# share.net
KiCad netlist of a schematic drawn in EasyEDA
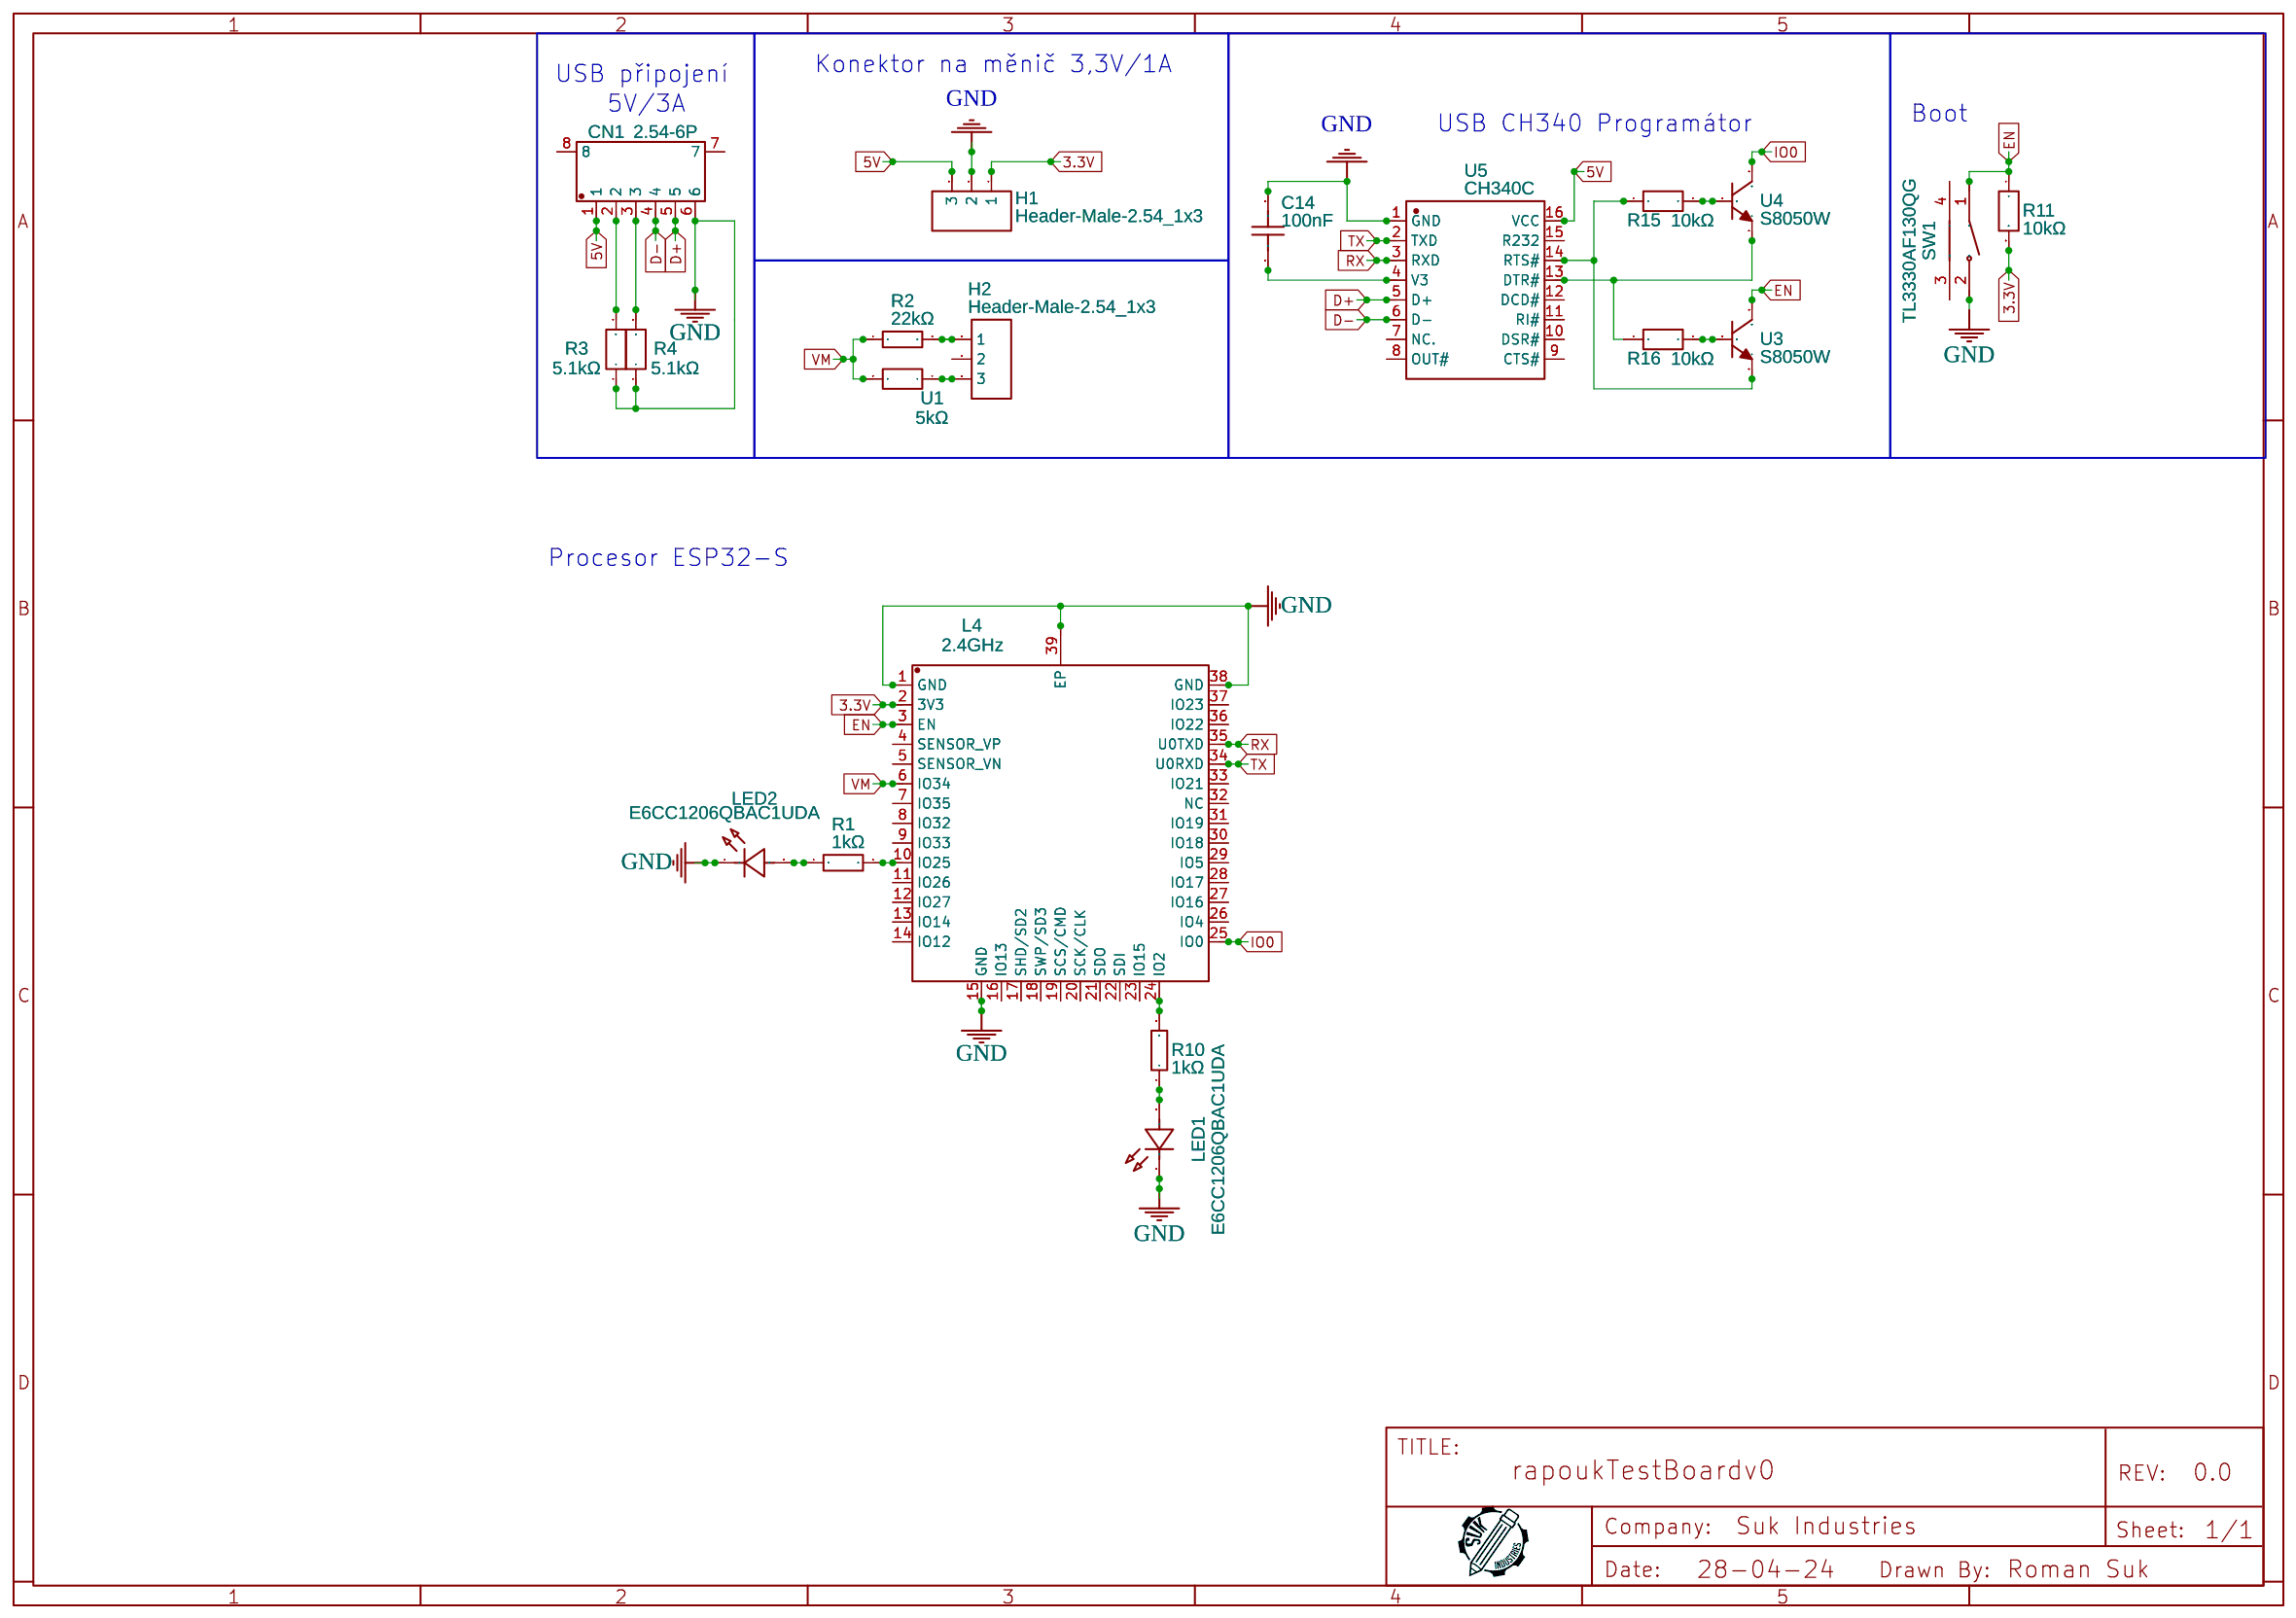
[diagram p0: schematic sheet]

(export (version "E")
  (design (tool "Eeschema 10.0.6"))
  (components
    (comp (ref "C14")
      (value "100nF")
      (fields
        (field (name "Manufacturer Part") "1206Y1000104KXR")
        (field (name "Manufacturer") "Knowles(楼氏)")
      )
      (libsource (lib "") (part "1206Y1000104KXR"))
    )
    (comp (ref "CN1")
      (value "2.54-6P")
      (fields (field (name "Manufacturer Part") "XH-6P卧贴") (field (name "Manufacturer") "BOOMELE(博穆精密)"))
      (libsource (lib "") (part "2.54-6P"))
    )
    (comp (ref "H1")
      (value "Header-Male-2.54_1x3")
      (fields (field (name "Manufacturer Part") "2.54-1*3P针") (field (name "Manufacturer") "BOOMELE(博穆精密)"))
      (libsource (lib "") (part "Header-Male-2.54_1x3_1"))
    )
    (comp (ref "H2")
      (value "Header-Male-2.54_1x3")
      (fields (field (name "Manufacturer Part") "2.54-1*3P针") (field (name "Manufacturer") "BOOMELE(博穆精密)"))
      (libsource (lib "") (part "Header-Male-2.54_1x3"))
    )
    (comp (ref "L4")
      (value "2.4GHz")
      (fields
        (field (name "Manufacturer Part") "ESP32-S(16MB)")
        (field (name "Manufacturer") "Ai-Thinker(安信可)")
      )
      (libsource (lib "") (part "ESP32-S(16MB)"))
    )
    (comp (ref "LED1")
      (value "E6CC1206QBAC1UDA")
      (fields (field (name "Manufacturer") "ekinglux(亿晶源)"))
      (libsource (lib "") (part "E6CC1206QBAC1UDA_1"))
    )
    (comp (ref "LED2")
      (value "E6CC1206QBAC1UDA")
      (fields (field (name "Manufacturer") "ekinglux(亿晶源)"))
      (libsource (lib "") (part "E6CC1206QBAC1UDA"))
    )
    (comp (ref "R1")
      (value "1kΩ")
      (fields (field (name "Manufacturer Part") "CR1206-FX-1001ELF") (field (name "Manufacturer") "BOURNS"))
      (libsource (lib "") (part "CR1206-FX-1001ELF"))
    )
    (comp (ref "R2")
      (value "22kΩ")
      (fields (field (name "Manufacturer Part") "AECR1206F22K0K9") (field (name "Manufacturer") "RESI(开步睿思）"))
      (libsource (lib "") (part "AECR1206F22K0K9"))
    )
    (comp (ref "R3")
      (value "5.1kΩ")
      (fields (field (name "Manufacturer Part") "FRC0603F5101TS") (field (name "Manufacturer") "FOJAN(富捷)"))
      (libsource (lib "") (part "FRC0603F5101TS"))
    )
    (comp (ref "R4")
      (value "5.1kΩ")
      (fields (field (name "Manufacturer Part") "FRC0603F5101TS") (field (name "Manufacturer") "FOJAN(富捷)"))
      (libsource (lib "") (part "FRC0603F5101TS"))
    )
    (comp (ref "R10")
      (value "1kΩ")
      (fields (field (name "Manufacturer Part") "CR1206-FX-1001ELF") (field (name "Manufacturer") "BOURNS"))
      (libsource (lib "") (part "CR1206-FX-1001ELF_1"))
    )
    (comp (ref "R11")
      (value "10kΩ")
      (fields (field (name "Manufacturer Part") "SCR1206F10K") (field (name "Manufacturer") "VO(翔胜)"))
      (libsource (lib "") (part "SCR1206F10K_1"))
    )
    (comp (ref "R15")
      (value "10kΩ")
      (fields (field (name "Manufacturer Part") "SCR1206F10K") (field (name "Manufacturer") "VO(翔胜)"))
      (libsource (lib "") (part "SCR1206F10K"))
    )
    (comp (ref "R16")
      (value "10kΩ")
      (fields (field (name "Manufacturer Part") "SCR1206F10K") (field (name "Manufacturer") "VO(翔胜)"))
      (libsource (lib "") (part "SCR1206F10K"))
    )
    (comp (ref "SW1")
      (value "TL3330AF130QG")
      (fields (field (name "Manufacturer") "E-Switch"))
      (libsource (lib "") (part "TL3330AF130QG"))
    )
    (comp (ref "U1")
      (value "5kΩ")
      (fields (field (name "Manufacturer Part") "HVF1206T5001FE") (field (name "Manufacturer") "Ohmite"))
      (libsource (lib "") (part "HVF1206T5001FE"))
    )
    (comp (ref "U3")
      (value "S8050W")
      (fields (field (name "Manufacturer") "Slkor(萨科微)"))
      (libsource (lib "") (part "S8050W"))
    )
    (comp (ref "U4")
      (value "S8050W")
      (fields (field (name "Manufacturer") "Slkor(萨科微)"))
      (libsource (lib "") (part "S8050W"))
    )
    (comp (ref "U5")
      (value "CH340C")
      (fields (field (name "Manufacturer") "WCH(南京沁恒)"))
      (libsource (lib "") (part "CH340C"))
    )
  )
  (nets
    (net (code "1") (name "3.3V") (class "Default")
      (node (ref "H1") (pin "1") (pinfunction "1_1") (pintype "input"))
      (node (ref "L4") (pin "2") (pinfunction "3V3_2") (pintype "unspecified"))
      (node (ref "R11") (pin "2") (pinfunction "2_2") (pintype "unspecified"))
    )
    (net (code "2") (name "5V") (class "Default")
      (node (ref "CN1") (pin "1") (pinfunction "1_1") (pintype "unspecified"))
      (node (ref "H1") (pin "3") (pinfunction "3_3") (pintype "input"))
      (node (ref "U5") (pin "16") (pinfunction "VCC_16") (pintype "unspecified"))
    )
    (net (code "3") (name "D+") (class "Default")
      (node (ref "CN1") (pin "5") (pinfunction "5_5") (pintype "unspecified"))
      (node (ref "U5") (pin "5") (pinfunction "D+_5") (pintype "unspecified"))
    )
    (net (code "4") (name "D-") (class "Default")
      (node (ref "CN1") (pin "4") (pinfunction "4_4") (pintype "unspecified"))
      (node (ref "U5") (pin "6") (pinfunction "D-_6") (pintype "unspecified"))
    )
    (net (code "5") (name "EN") (class "Default")
      (node (ref "L4") (pin "3") (pinfunction "EN_3") (pintype "unspecified"))
      (node (ref "R11") (pin "1") (pinfunction "1_1") (pintype "unspecified"))
      (node (ref "SW1") (pin "1") (pinfunction "1_1") (pintype "unspecified"))
      (node (ref "U3") (pin "3") (pinfunction "C_3") (pintype "unspecified"))
    )
    (net (code "6") (name "GND") (class "Default")
      (node (ref "C14") (pin "2") (pinfunction "2_2") (pintype "unspecified"))
      (node (ref "CN1") (pin "6") (pinfunction "6_6") (pintype "unspecified"))
      (node (ref "H1") (pin "2") (pinfunction "2_2") (pintype "input"))
      (node (ref "L4") (pin "1") (pinfunction "GND_1") (pintype "unspecified"))
      (node (ref "L4") (pin "15") (pinfunction "GND_15") (pintype "unspecified"))
      (node (ref "L4") (pin "38") (pinfunction "GND_38") (pintype "unspecified"))
      (node (ref "L4") (pin "39") (pinfunction "EP_39") (pintype "unspecified"))
      (node (ref "LED1") (pin "1") (pinfunction "K_1") (pintype "unspecified"))
      (node (ref "LED2") (pin "1") (pinfunction "K_1") (pintype "unspecified"))
      (node (ref "R3") (pin "1") (pinfunction "1_1") (pintype "unspecified"))
      (node (ref "R4") (pin "1") (pinfunction "1_1") (pintype "unspecified"))
      (node (ref "SW1") (pin "2") (pinfunction "2_2") (pintype "unspecified"))
      (node (ref "U5") (pin "1") (pinfunction "GND_1") (pintype "unspecified"))
    )
    (net (code "7") (name "IO0") (class "Default")
      (node (ref "L4") (pin "25") (pinfunction "IO0_25") (pintype "unspecified"))
      (node (ref "U4") (pin "3") (pinfunction "C_3") (pintype "unspecified"))
    )
    (net (code "8") (name "Net-(CN1-Pad2)") (class "Default")
      (node (ref "CN1") (pin "2") (pinfunction "2_2") (pintype "unspecified"))
      (node (ref "R3") (pin "2") (pinfunction "2_2") (pintype "unspecified"))
    )
    (net (code "9") (name "Net-(CN1-Pad3)") (class "Default")
      (node (ref "CN1") (pin "3") (pinfunction "3_3") (pintype "unspecified"))
      (node (ref "R4") (pin "2") (pinfunction "2_2") (pintype "unspecified"))
    )
    (net (code "10") (name "Net-(H2-Pad1)") (class "Default")
      (node (ref "H2") (pin "1") (pinfunction "1_1") (pintype "input"))
      (node (ref "R2") (pin "2") (pinfunction "2_2") (pintype "unspecified"))
    )
    (net (code "11") (name "Net-(H2-Pad3)") (class "Default")
      (node (ref "H2") (pin "3") (pinfunction "3_3") (pintype "input"))
      (node (ref "U1") (pin "1") (pinfunction "1_1") (pintype "unspecified"))
    )
    (net (code "12") (name "Net-(L4-IO2)") (class "Default")
      (node (ref "L4") (pin "24") (pinfunction "IO2_24") (pintype "unspecified"))
      (node (ref "R10") (pin "2") (pinfunction "2_2") (pintype "unspecified"))
    )
    (net (code "13") (name "Net-(L4-IO25)") (class "Default")
      (node (ref "L4") (pin "10") (pinfunction "IO25_10") (pintype "unspecified"))
      (node (ref "R1") (pin "2") (pinfunction "2_2") (pintype "unspecified"))
    )
    (net (code "14") (name "Net-(LED1-A)") (class "Default")
      (node (ref "LED1") (pin "2") (pinfunction "A_2") (pintype "unspecified"))
      (node (ref "R10") (pin "1") (pinfunction "1_1") (pintype "unspecified"))
    )
    (net (code "15") (name "Net-(LED2-A)") (class "Default")
      (node (ref "LED2") (pin "2") (pinfunction "A_2") (pintype "unspecified"))
      (node (ref "R1") (pin "1") (pinfunction "1_1") (pintype "unspecified"))
    )
    (net (code "16") (name "Net-(U3-B)") (class "Default")
      (node (ref "R16") (pin "2") (pinfunction "2_2") (pintype "unspecified"))
      (node (ref "U3") (pin "1") (pinfunction "B_1") (pintype "unspecified"))
    )
    (net (code "17") (name "Net-(U3-E)") (class "Default")
      (node (ref "R15") (pin "1") (pinfunction "1_1") (pintype "unspecified"))
      (node (ref "U3") (pin "2") (pinfunction "E_2") (pintype "unspecified"))
      (node (ref "U5") (pin "14") (pinfunction "RTS#_14") (pintype "unspecified"))
    )
    (net (code "18") (name "Net-(U4-B)") (class "Default")
      (node (ref "R15") (pin "2") (pinfunction "2_2") (pintype "unspecified"))
      (node (ref "U4") (pin "1") (pinfunction "B_1") (pintype "unspecified"))
    )
    (net (code "19") (name "Net-(U4-E)") (class "Default")
      (node (ref "R16") (pin "1") (pinfunction "1_1") (pintype "unspecified"))
      (node (ref "U4") (pin "2") (pinfunction "E_2") (pintype "unspecified"))
      (node (ref "U5") (pin "13") (pinfunction "DTR#_13") (pintype "unspecified"))
    )
    (net (code "20") (name "Net-(U5-V3)") (class "Default")
      (node (ref "C14") (pin "1") (pinfunction "1_1") (pintype "unspecified"))
      (node (ref "U5") (pin "4") (pinfunction "V3_4") (pintype "unspecified"))
    )
    (net (code "21") (name "RX") (class "Default")
      (node (ref "L4") (pin "35") (pinfunction "U0TXD_35") (pintype "unspecified"))
      (node (ref "U5") (pin "3") (pinfunction "RXD_3") (pintype "unspecified"))
    )
    (net (code "22") (name "TX") (class "Default")
      (node (ref "L4") (pin "34") (pinfunction "U0RXD_34") (pintype "unspecified"))
      (node (ref "U5") (pin "2") (pinfunction "TXD_2") (pintype "unspecified"))
    )
    (net (code "23") (name "VM") (class "Default")
      (node (ref "L4") (pin "6") (pinfunction "IO34_6") (pintype "unspecified"))
      (node (ref "R2") (pin "1") (pinfunction "1_1") (pintype "unspecified"))
      (node (ref "U1") (pin "2") (pinfunction "2_2") (pintype "unspecified"))
    )
    (net (code "24") (name "unconnected-(CN1-Pad7)") (class "Default")
      (node (ref "CN1") (pin "7") (pinfunction "7_7") (pintype "unspecified"))
    )
    (net (code "25") (name "unconnected-(CN1-Pad8)") (class "Default")
      (node (ref "CN1") (pin "8") (pinfunction "8_8") (pintype "unspecified"))
    )
    (net (code "26") (name "unconnected-(H2-Pad2)") (class "Default")
      (node (ref "H2") (pin "2") (pinfunction "2_2") (pintype "input"))
    )
    (net (code "27") (name "unconnected-(L4-IO4-Pad26)") (class "Default")
      (node (ref "L4") (pin "26") (pinfunction "IO4_26") (pintype "unspecified"))
    )
    (net (code "28") (name "unconnected-(L4-IO5-Pad29)") (class "Default")
      (node (ref "L4") (pin "29") (pinfunction "IO5_29") (pintype "unspecified"))
    )
    (net (code "29") (name "unconnected-(L4-IO12-Pad14)") (class "Default")
      (node (ref "L4") (pin "14") (pinfunction "IO12_14") (pintype "unspecified"))
    )
    (net (code "30") (name "unconnected-(L4-IO13-Pad16)") (class "Default")
      (node (ref "L4") (pin "16") (pinfunction "IO13_16") (pintype "unspecified"))
    )
    (net (code "31") (name "unconnected-(L4-IO14-Pad13)") (class "Default")
      (node (ref "L4") (pin "13") (pinfunction "IO14_13") (pintype "unspecified"))
    )
    (net (code "32") (name "unconnected-(L4-IO15-Pad23)") (class "Default")
      (node (ref "L4") (pin "23") (pinfunction "IO15_23") (pintype "unspecified"))
    )
    (net (code "33") (name "unconnected-(L4-IO16-Pad27)") (class "Default")
      (node (ref "L4") (pin "27") (pinfunction "IO16_27") (pintype "unspecified"))
    )
    (net (code "34") (name "unconnected-(L4-IO17-Pad28)") (class "Default")
      (node (ref "L4") (pin "28") (pinfunction "IO17_28") (pintype "unspecified"))
    )
    (net (code "35") (name "unconnected-(L4-IO18-Pad30)") (class "Default")
      (node (ref "L4") (pin "30") (pinfunction "IO18_30") (pintype "unspecified"))
    )
    (net (code "36") (name "unconnected-(L4-IO19-Pad31)") (class "Default")
      (node (ref "L4") (pin "31") (pinfunction "IO19_31") (pintype "unspecified"))
    )
    (net (code "37") (name "unconnected-(L4-IO21-Pad33)") (class "Default")
      (node (ref "L4") (pin "33") (pinfunction "IO21_33") (pintype "unspecified"))
    )
    (net (code "38") (name "unconnected-(L4-IO22-Pad36)") (class "Default")
      (node (ref "L4") (pin "36") (pinfunction "IO22_36") (pintype "unspecified"))
    )
    (net (code "39") (name "unconnected-(L4-IO23-Pad37)") (class "Default")
      (node (ref "L4") (pin "37") (pinfunction "IO23_37") (pintype "unspecified"))
    )
    (net (code "40") (name "unconnected-(L4-IO26-Pad11)") (class "Default")
      (node (ref "L4") (pin "11") (pinfunction "IO26_11") (pintype "unspecified"))
    )
    (net (code "41") (name "unconnected-(L4-IO27-Pad12)") (class "Default")
      (node (ref "L4") (pin "12") (pinfunction "IO27_12") (pintype "unspecified"))
    )
    (net (code "42") (name "unconnected-(L4-IO32-Pad8)") (class "Default")
      (node (ref "L4") (pin "8") (pinfunction "IO32_8") (pintype "unspecified"))
    )
    (net (code "43") (name "unconnected-(L4-IO33-Pad9)") (class "Default")
      (node (ref "L4") (pin "9") (pinfunction "IO33_9") (pintype "unspecified"))
    )
    (net (code "44") (name "unconnected-(L4-IO35-Pad7)") (class "Default")
      (node (ref "L4") (pin "7") (pinfunction "IO35_7") (pintype "unspecified"))
    )
    (net (code "45") (name "unconnected-(L4-NC-Pad32)") (class "Default")
      (node (ref "L4") (pin "32") (pinfunction "NC_32") (pintype "unspecified"))
    )
    (net (code "46") (name "unconnected-(L4-SCK{slash}CLK-Pad20)") (class "Default")
      (node (ref "L4") (pin "20") (pinfunction "SCK/CLK_20") (pintype "unspecified"))
    )
    (net (code "47") (name "unconnected-(L4-SCS{slash}CMD-Pad19)") (class "Default")
      (node (ref "L4") (pin "19") (pinfunction "SCS/CMD_19") (pintype "unspecified"))
    )
    (net (code "48") (name "unconnected-(L4-SDI-Pad22)") (class "Default")
      (node (ref "L4") (pin "22") (pinfunction "SDI_22") (pintype "unspecified"))
    )
    (net (code "49") (name "unconnected-(L4-SDO-Pad21)") (class "Default")
      (node (ref "L4") (pin "21") (pinfunction "SDO_21") (pintype "unspecified"))
    )
    (net (code "50") (name "unconnected-(L4-SENSOR_VN-Pad5)") (class "Default")
      (node (ref "L4") (pin "5") (pinfunction "SENSOR_VN_5") (pintype "unspecified"))
    )
    (net (code "51") (name "unconnected-(L4-SENSOR_VP-Pad4)") (class "Default")
      (node (ref "L4") (pin "4") (pinfunction "SENSOR_VP_4") (pintype "unspecified"))
    )
    (net (code "52") (name "unconnected-(L4-SHD{slash}SD2-Pad17)") (class "Default")
      (node (ref "L4") (pin "17") (pinfunction "SHD/SD2_17") (pintype "unspecified"))
    )
    (net (code "53") (name "unconnected-(L4-SWP{slash}SD3-Pad18)") (class "Default")
      (node (ref "L4") (pin "18") (pinfunction "SWP/SD3_18") (pintype "unspecified"))
    )
    (net (code "54") (name "unconnected-(SW1-Pad3)") (class "Default")
      (node (ref "SW1") (pin "3") (pinfunction "3_3") (pintype "unspecified"))
    )
    (net (code "55") (name "unconnected-(SW1-Pad4)") (class "Default")
      (node (ref "SW1") (pin "4") (pinfunction "4_4") (pintype "unspecified"))
    )
    (net (code "56") (name "unconnected-(U5-CTS#-Pad9)") (class "Default")
      (node (ref "U5") (pin "9") (pinfunction "CTS#_9") (pintype "unspecified"))
    )
    (net (code "57") (name "unconnected-(U5-DCD#-Pad12)") (class "Default")
      (node (ref "U5") (pin "12") (pinfunction "DCD#_12") (pintype "unspecified"))
    )
    (net (code "58") (name "unconnected-(U5-DSR#-Pad10)") (class "Default")
      (node (ref "U5") (pin "10") (pinfunction "DSR#_10") (pintype "unspecified"))
    )
    (net (code "59") (name "unconnected-(U5-NC.-Pad7)") (class "Default")
      (node (ref "U5") (pin "7") (pinfunction "NC._7") (pintype "unspecified"))
    )
    (net (code "60") (name "unconnected-(U5-OUT#-Pad8)") (class "Default")
      (node (ref "U5") (pin "8") (pinfunction "OUT#_8") (pintype "unspecified"))
    )
    (net (code "61") (name "unconnected-(U5-R232-Pad15)") (class "Default")
      (node (ref "U5") (pin "15") (pinfunction "R232_15") (pintype "unspecified"))
    )
    (net (code "62") (name "unconnected-(U5-RI#-Pad11)") (class "Default")
      (node (ref "U5") (pin "11") (pinfunction "RI#_11") (pintype "unspecified"))
    )
  )
)
